# Wireless_Lora.net
KiCad netlist of a schematic drawn in Altium Designer
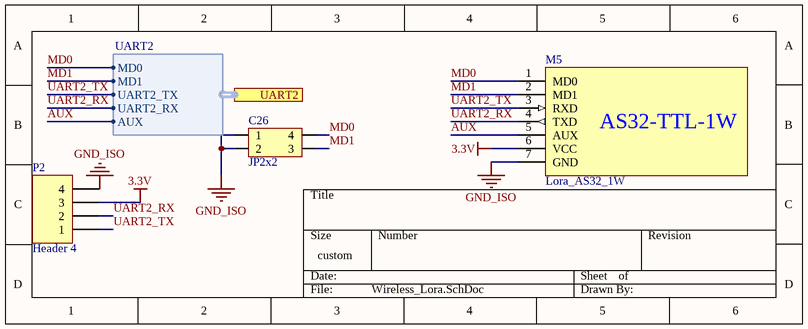
[diagram p0: Wireless_Lora.SchDoc]

(export (version "E")
  (design (tool "Eeschema 10.0.6"))
  (components
    (comp (ref "C26")
      (value "JP2x2")
      (footprint "JP2-D2T")
      (description "WR-PHD 2.54 mm Dual Socket Header")
      (fields
        (field (name "MANUFACTURER") "Würth Elektronik eiSos GmbH")
        (field (name "PARTNO") "61300421821")
        (field (name "CREATED BY") "Karrer Zheng")
      )
      (libsource (lib "thu vien 3d") (part "JP2x2"))
    )
    (comp (ref "M5")
      (value "Lora_AS32_1W")
      (footprint "LORA_AS32-TTL-1W")
      (libsource (lib "All Library") (part "Lora_AS32_1W"))
    )
    (comp (ref "P2")
      (value "Header 4")
      (footprint "HDR1X4")
      (description "Header, 4-Pin")
      (fields (field (name "PUBLISHER") "Altium Limited"))
      (libsource (lib "Miscellaneous Connectors") (part "Header 4"))
    )
  )
  (nets
    (net (code "2") (name "/AUX") (class "Default")
      (node (ref "M5") (pin "5") (pinfunction "AUX_5") (pintype "passive"))
    )
    (net (code "3") (name "/MD0") (class "Default")
      (node (ref "C26") (pin "4") (pinfunction "4_4") (pintype "passive"))
      (node (ref "M5") (pin "1") (pinfunction "MD0_1") (pintype "passive"))
    )
    (net (code "4") (name "/MD1") (class "Default")
      (node (ref "C26") (pin "3") (pinfunction "3_3") (pintype "passive"))
      (node (ref "M5") (pin "2") (pinfunction "MD1_2") (pintype "passive"))
    )
    (net (code "5") (name "/UART2_RX") (class "Default")
      (node (ref "M5") (pin "4") (pinfunction "TXD_4") (pintype "output"))
      (node (ref "P2") (pin "2") (pinfunction "2_2") (pintype "passive"))
    )
    (net (code "6") (name "/UART2_TX") (class "Default")
      (node (ref "M5") (pin "3") (pinfunction "RXD_3") (pintype "input"))
      (node (ref "P2") (pin "1") (pinfunction "1_1") (pintype "passive"))
    )
    (net (code "8") (name "3.3V") (class "Default")
      (node (ref "M5") (pin "6") (pinfunction "VCC_6") (pintype "power_in"))
      (node (ref "P2") (pin "3") (pinfunction "3_3") (pintype "passive"))
    )
    (net (code "9") (name "GND_ISO") (class "Default")
      (node (ref "C26") (pin "1") (pinfunction "1_1") (pintype "passive"))
      (node (ref "C26") (pin "2") (pinfunction "2_2") (pintype "passive"))
      (node (ref "M5") (pin "7") (pinfunction "GND_7") (pintype "power_in"))
      (node (ref "P2") (pin "4") (pinfunction "4_4") (pintype "passive"))
    )
  )
)
